# SMD_optek_led-mosfet.net
KiCad netlist of a schematic drawn in EAGLE
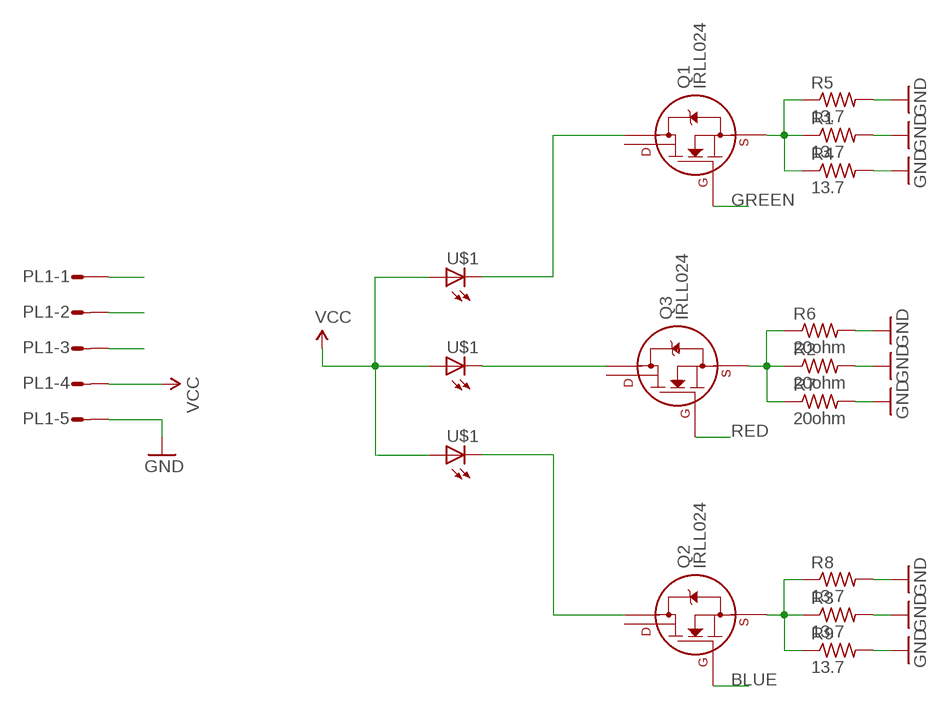
[diagram p0: schematic, sheet 1]

(export (version "E")
  (design (tool "Eeschema 10.0.6"))
  (components
    (comp (ref "PL1")
      (value "DF3-05R")
      (footprint "eagle-import:DF3R-05")
      (libsource (lib "eagle-import") (part "DF3-05R"))
    )
    (comp (ref "Q1")
      (value "IRLL024")
      (footprint "eagle-import:SOT-223")
      (libsource (lib "eagle-import") (part "IRLL024"))
    )
    (comp (ref "Q2")
      (value "IRLL024")
      (footprint "eagle-import:SOT-223")
      (libsource (lib "eagle-import") (part "IRLL024"))
    )
    (comp (ref "Q3")
      (value "IRLL024")
      (footprint "eagle-import:SOT-223")
      (libsource (lib "eagle-import") (part "IRLL024"))
    )
    (comp (ref "R1")
      (value "13.7")
      (footprint "eagle-import:R1210")
      (libsource (lib "eagle-import") (part "R-US_R1210"))
    )
    (comp (ref "R2")
      (value "20ohm")
      (footprint "eagle-import:R1210")
      (libsource (lib "eagle-import") (part "R-US_R1210"))
    )
    (comp (ref "R3")
      (value "13.7")
      (footprint "eagle-import:R1210")
      (libsource (lib "eagle-import") (part "R-US_R1210"))
    )
    (comp (ref "R4")
      (value "13.7")
      (footprint "eagle-import:R1210")
      (libsource (lib "eagle-import") (part "R-US_R1210"))
    )
    (comp (ref "R5")
      (value "13.7")
      (footprint "eagle-import:R1210")
      (libsource (lib "eagle-import") (part "R-US_R1210"))
    )
    (comp (ref "R6")
      (value "20ohm")
      (footprint "eagle-import:R1210")
      (libsource (lib "eagle-import") (part "R-US_R1210"))
    )
    (comp (ref "R7")
      (value "20ohm")
      (footprint "eagle-import:R1210")
      (libsource (lib "eagle-import") (part "R-US_R1210"))
    )
    (comp (ref "R8")
      (value "13.7")
      (footprint "eagle-import:R1210")
      (libsource (lib "eagle-import") (part "R-US_R1210"))
    )
    (comp (ref "R9")
      (value "13.7")
      (footprint "eagle-import:R1210")
      (libsource (lib "eagle-import") (part "R-US_R1210"))
    )
    (comp (ref "U$1")
      (value "OVSPRGBCR4")
      (footprint "eagle-import:OVSPRGBCR4")
      (libsource (lib "eagle-import") (part "OVSPRGBCR4"))
    )
  )
  (nets
    (net (code "1") (name "/BLUE") (class "Default")
      (node (ref "PL1") (pin "3") (pinfunction "S_3") (pintype "passive"))
      (node (ref "Q2") (pin "1") (pinfunction "G_1") (pintype "tri_state"))
    )
    (net (code "2") (name "/GREEN") (class "Default")
      (node (ref "PL1") (pin "1") (pinfunction "S_1") (pintype "passive"))
      (node (ref "Q1") (pin "1") (pinfunction "G_1") (pintype "tri_state"))
    )
    (net (code "3") (name "/RED") (class "Default")
      (node (ref "PL1") (pin "2") (pinfunction "S_2") (pintype "passive"))
      (node (ref "Q3") (pin "1") (pinfunction "G_1") (pintype "tri_state"))
    )
    (net (code "4") (name "GND") (class "Default")
      (node (ref "PL1") (pin "5") (pinfunction "S_5") (pintype "passive"))
      (node (ref "R1") (pin "2") (pinfunction "2_2") (pintype "passive"))
      (node (ref "R2") (pin "2") (pinfunction "2_2") (pintype "passive"))
      (node (ref "R3") (pin "2") (pinfunction "2_2") (pintype "passive"))
      (node (ref "R4") (pin "2") (pinfunction "2_2") (pintype "passive"))
      (node (ref "R5") (pin "2") (pinfunction "2_2") (pintype "passive"))
      (node (ref "R6") (pin "2") (pinfunction "2_2") (pintype "passive"))
      (node (ref "R7") (pin "2") (pinfunction "2_2") (pintype "passive"))
      (node (ref "R8") (pin "2") (pinfunction "2_2") (pintype "passive"))
      (node (ref "R9") (pin "2") (pinfunction "2_2") (pintype "passive"))
    )
    (net (code "5") (name "Net-(Q1-D1)") (class "Default")
      (node (ref "Q1") (pin "2") (pinfunction "D1_2") (pintype "bidirectional"))
      (node (ref "U$1") (pin "6") (pinfunction "GREEN_C_6") (pintype "passive"))
    )
    (net (code "6") (name "Net-(Q1-S)") (class "Default")
      (node (ref "Q1") (pin "3") (pinfunction "S_3") (pintype "bidirectional"))
      (node (ref "R1") (pin "1") (pinfunction "1_1") (pintype "passive"))
      (node (ref "R4") (pin "1") (pinfunction "1_1") (pintype "passive"))
      (node (ref "R5") (pin "1") (pinfunction "1_1") (pintype "passive"))
    )
    (net (code "7") (name "Net-(Q2-D1)") (class "Default")
      (node (ref "Q2") (pin "2") (pinfunction "D1_2") (pintype "bidirectional"))
      (node (ref "U$1") (pin "4") (pinfunction "BLUE_C_4") (pintype "passive"))
    )
    (net (code "8") (name "Net-(Q2-S)") (class "Default")
      (node (ref "Q2") (pin "3") (pinfunction "S_3") (pintype "bidirectional"))
      (node (ref "R3") (pin "1") (pinfunction "1_1") (pintype "passive"))
      (node (ref "R8") (pin "1") (pinfunction "1_1") (pintype "passive"))
      (node (ref "R9") (pin "1") (pinfunction "1_1") (pintype "passive"))
    )
    (net (code "9") (name "Net-(Q3-D1)") (class "Default")
      (node (ref "Q3") (pin "2") (pinfunction "D1_2") (pintype "bidirectional"))
      (node (ref "U$1") (pin "5") (pinfunction "RED_C_5") (pintype "passive"))
    )
    (net (code "10") (name "Net-(Q3-S)") (class "Default")
      (node (ref "Q3") (pin "3") (pinfunction "S_3") (pintype "bidirectional"))
      (node (ref "R2") (pin "1") (pinfunction "1_1") (pintype "passive"))
      (node (ref "R6") (pin "1") (pinfunction "1_1") (pintype "passive"))
      (node (ref "R7") (pin "1") (pinfunction "1_1") (pintype "passive"))
    )
    (net (code "11") (name "VCC") (class "Default")
      (node (ref "PL1") (pin "4") (pinfunction "S_4") (pintype "passive"))
      (node (ref "U$1") (pin "1") (pinfunction "GREEN_A_1") (pintype "passive"))
      (node (ref "U$1") (pin "2") (pinfunction "RED_A_2") (pintype "passive"))
      (node (ref "U$1") (pin "3") (pinfunction "BLUE_A_3") (pintype "passive"))
    )
    (net (code "12") (name "unconnected-(Q1-D2-Pad4)") (class "Default")
      (node (ref "Q1") (pin "4") (pinfunction "D2_4") (pintype "bidirectional"))
    )
    (net (code "13") (name "unconnected-(Q2-D2-Pad4)") (class "Default")
      (node (ref "Q2") (pin "4") (pinfunction "D2_4") (pintype "bidirectional"))
    )
    (net (code "14") (name "unconnected-(Q3-D2-Pad4)") (class "Default")
      (node (ref "Q3") (pin "4") (pinfunction "D2_4") (pintype "bidirectional"))
    )
  )
)
